# Redesign-8Ch-Mux-Breakout-PMODIA.net
KiCad netlist of a schematic drawn in EAGLE
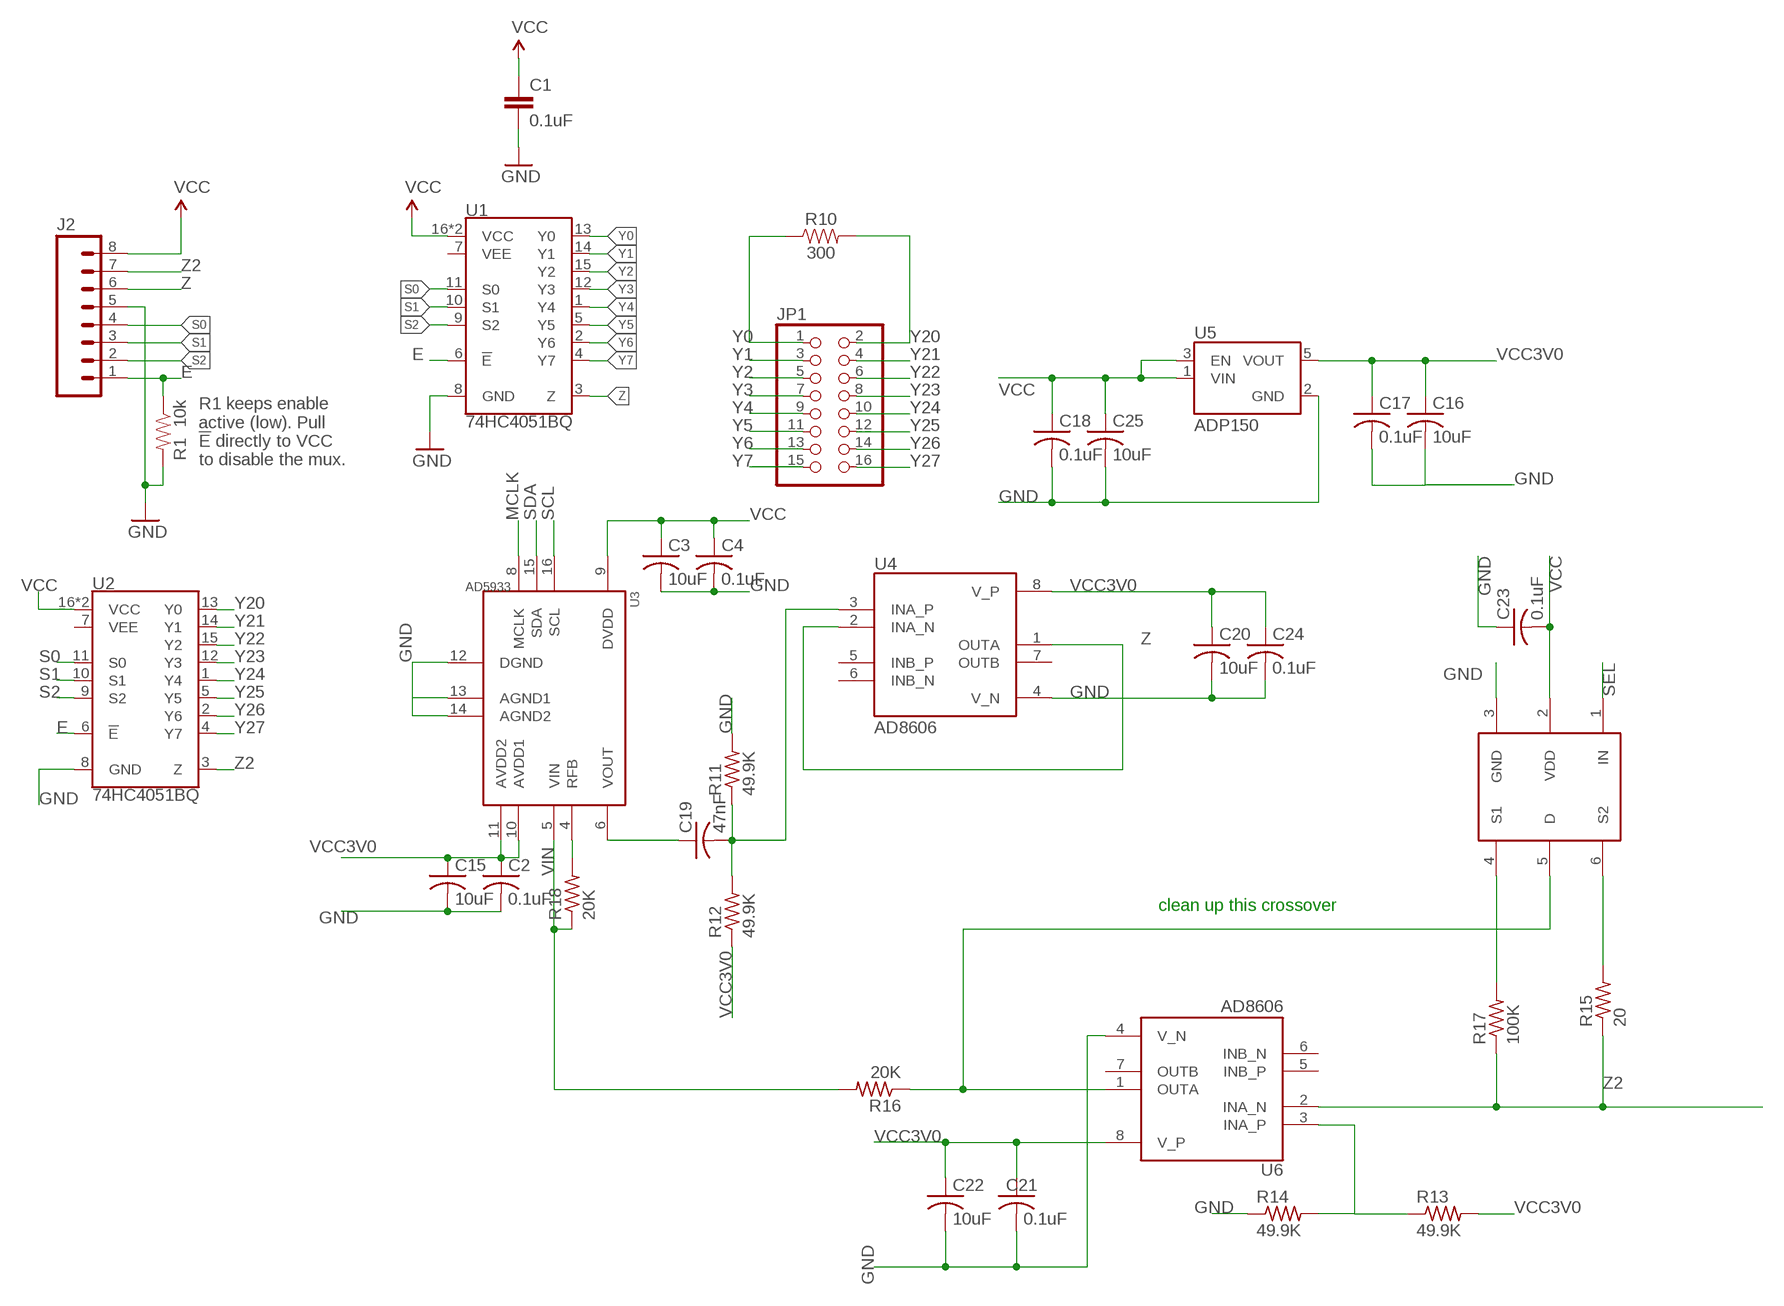
[diagram p0: schematic, sheet 1]

(export (version "E")
  (design (tool "Eeschema 10.0.6"))
  (components
    (comp (ref "C1")
      (value "0.1uF")
      (footprint "eagle-import:0603")
      (libsource (lib "eagle-import") (part "0.1UF-0603-25V-(+80/-20%)"))
    )
    (comp (ref "C2")
      (value "0.1uF")
      (footprint "eagle-import:C0805K")
      (libsource (lib "eagle-import") (part "C-USC0805K"))
    )
    (comp (ref "C3")
      (value "10uF")
      (footprint "eagle-import:C0805K")
      (libsource (lib "eagle-import") (part "C-USC0805K"))
    )
    (comp (ref "C4")
      (value "0.1uF")
      (footprint "eagle-import:C0805K")
      (libsource (lib "eagle-import") (part "C-USC0805K"))
    )
    (comp (ref "C15")
      (value "10uF")
      (footprint "eagle-import:C0805K")
      (libsource (lib "eagle-import") (part "C-USC0805K"))
    )
    (comp (ref "C16")
      (value "10uF")
      (footprint "eagle-import:C0805K")
      (libsource (lib "eagle-import") (part "C-USC0805K"))
    )
    (comp (ref "C17")
      (value "0.1uF")
      (footprint "eagle-import:C0805K")
      (libsource (lib "eagle-import") (part "C-USC0805K"))
    )
    (comp (ref "C18")
      (value "0.1uF")
      (footprint "eagle-import:C0805K")
      (libsource (lib "eagle-import") (part "C-USC0805K"))
    )
    (comp (ref "C19")
      (value "47nF")
      (footprint "eagle-import:C0805K")
      (libsource (lib "eagle-import") (part "C-USC0805K"))
    )
    (comp (ref "C20")
      (value "10uF")
      (footprint "eagle-import:C0805K")
      (libsource (lib "eagle-import") (part "C-USC0805K"))
    )
    (comp (ref "C21")
      (value "0.1uF")
      (footprint "eagle-import:C0805K")
      (libsource (lib "eagle-import") (part "C-USC0805K"))
    )
    (comp (ref "C22")
      (value "10uF")
      (footprint "eagle-import:C0805K")
      (libsource (lib "eagle-import") (part "C-USC0805K"))
    )
    (comp (ref "C23")
      (value "0.1uF")
      (footprint "eagle-import:C0805K")
      (libsource (lib "eagle-import") (part "C-USC0805K"))
    )
    (comp (ref "C24")
      (value "0.1uF")
      (footprint "eagle-import:C0805K")
      (libsource (lib "eagle-import") (part "C-USC0805K"))
    )
    (comp (ref "C25")
      (value "10uF")
      (footprint "eagle-import:C0805K")
      (libsource (lib "eagle-import") (part "C-USC0805K"))
    )
    (comp (ref "J2")
      (value "M08")
      (footprint "eagle-import:1X08_ROUND")
      (libsource (lib "eagle-import") (part "M08"))
    )
    (comp (ref "JP1")
      (value "PINHD-2X8")
      (footprint "eagle-import:2X08")
      (libsource (lib "eagle-import") (part "PINHD-2X8"))
    )
    (comp (ref "R1")
      (value "10k")
      (footprint "eagle-import:0603")
      (libsource (lib "eagle-import") (part "10KOHM-0603-1/10W-1%"))
    )
    (comp (ref "R10")
      (value "300")
      (footprint "eagle-import:0805")
      (libsource (lib "eagle-import") (part "0.3OHM-0805-1/8W-1%"))
    )
    (comp (ref "R11")
      (value "49.9K")
      (footprint "eagle-import:R0603")
      (libsource (lib "eagle-import") (part "R-US_R0603"))
    )
    (comp (ref "R12")
      (value "49.9K")
      (footprint "eagle-import:R0603")
      (libsource (lib "eagle-import") (part "R-US_R0603"))
    )
    (comp (ref "R13")
      (value "49.9K")
      (footprint "eagle-import:R0603")
      (libsource (lib "eagle-import") (part "R-US_R0603"))
    )
    (comp (ref "R14")
      (value "49.9K")
      (footprint "eagle-import:R0603")
      (libsource (lib "eagle-import") (part "R-US_R0603"))
    )
    (comp (ref "R15")
      (value "20")
      (footprint "eagle-import:R0603")
      (libsource (lib "eagle-import") (part "R-US_R0603"))
    )
    (comp (ref "R16")
      (value "20K")
      (footprint "eagle-import:R0603")
      (libsource (lib "eagle-import") (part "R-US_R0603"))
    )
    (comp (ref "R17")
      (value "100K")
      (footprint "eagle-import:R0603")
      (libsource (lib "eagle-import") (part "R-US_R0603"))
    )
    (comp (ref "R18")
      (value "20K")
      (footprint "eagle-import:R0603")
      (libsource (lib "eagle-import") (part "R-US_R0603"))
    )
    (comp (ref "U$1")
      (value "ADG849THROUHG_HOLE")
      (footprint "eagle-import:SOT65P210X110-6N")
      (libsource (lib "eagle-import") (part "ADG849THROUHG_HOLE"))
    )
    (comp (ref "U1")
      (value "74HC4051BQ")
      (footprint "eagle-import:DHVQFN-16-2.5X3.5MM")
      (libsource (lib "eagle-import") (part "74HC4051BQ"))
    )
    (comp (ref "U2")
      (value "74HC4051BQ")
      (footprint "eagle-import:DHVQFN-16-2.5X3.5MM")
      (libsource (lib "eagle-import") (part "74HC4051BQ"))
    )
    (comp (ref "U3")
      (value "AD5933")
      (footprint "eagle-import:SSOP16")
      (libsource (lib "eagle-import") (part "AD5933"))
    )
    (comp (ref "U4")
      (value "AD8606")
      (footprint "eagle-import:SOIC-8")
      (fields (field (name "MF") "Analog Devices") (field (name "MP") "AD8606ARZ"))
      (libsource (lib "eagle-import") (part "Updated PMODIA_AD8606"))
    )
    (comp (ref "U5")
      (value "ADP150")
      (footprint "eagle-import:SOT95P280X100-5N")
      (fields (field (name "MF") "Analog Devices") (field (name "MP") "ADP150AUJZ-2.0-R7"))
      (libsource (lib "eagle-import") (part "ADP150"))
    )
    (comp (ref "U6")
      (value "AD8606")
      (footprint "eagle-import:SOIC-8")
      (fields (field (name "MF") "Analog Devices") (field (name "MP") "AD8606ARZ"))
      (libsource (lib "eagle-import") (part "Updated PMODIA_AD8606"))
    )
  )
  (nets
    (net (code "1") (name "/E") (class "Default")
      (node (ref "J2") (pin "1") (pinfunction "1_1") (pintype "passive"))
      (node (ref "R1") (pin "1") (pinfunction "1_1") (pintype "passive"))
      (node (ref "U1") (pin "6") (pinfunction "~{E}_6") (pintype "bidirectional"))
      (node (ref "U2") (pin "6") (pinfunction "~{E}_6") (pintype "bidirectional"))
    )
    (net (code "2") (name "/MCLK") (class "Default")
      (node (ref "U3") (pin "8") (pinfunction "MCLK_8") (pintype "bidirectional"))
    )
    (net (code "3") (name "/SCL") (class "Default")
      (node (ref "U3") (pin "16") (pinfunction "SCL_16") (pintype "bidirectional"))
    )
    (net (code "4") (name "/SDA") (class "Default")
      (node (ref "U3") (pin "15") (pinfunction "SDA_15") (pintype "bidirectional"))
    )
    (net (code "5") (name "/SEL") (class "Default")
      (node (ref "U$1") (pin "1") (pinfunction "IN_1") (pintype "bidirectional"))
    )
    (net (code "6") (name "/VCC3V0") (class "Default")
      (node (ref "C15") (pin "1") (pinfunction "1_1") (pintype "passive"))
      (node (ref "C16") (pin "1") (pinfunction "1_1") (pintype "passive"))
      (node (ref "C17") (pin "1") (pinfunction "1_1") (pintype "passive"))
      (node (ref "C2") (pin "1") (pinfunction "1_1") (pintype "passive"))
      (node (ref "C20") (pin "1") (pinfunction "1_1") (pintype "passive"))
      (node (ref "C21") (pin "1") (pinfunction "1_1") (pintype "passive"))
      (node (ref "C22") (pin "1") (pinfunction "1_1") (pintype "passive"))
      (node (ref "C24") (pin "1") (pinfunction "1_1") (pintype "passive"))
      (node (ref "R12") (pin "1") (pinfunction "1_1") (pintype "passive"))
      (node (ref "R13") (pin "2") (pinfunction "2_2") (pintype "passive"))
      (node (ref "U3") (pin "10") (pinfunction "AVDD1_10") (pintype "bidirectional"))
      (node (ref "U3") (pin "11") (pinfunction "AVDD2_11") (pintype "bidirectional"))
      (node (ref "U4") (pin "8") (pinfunction "V_P_8") (pintype "power_in"))
      (node (ref "U5") (pin "5") (pinfunction "VOUT_5") (pintype "output"))
      (node (ref "U6") (pin "8") (pinfunction "V_P_8") (pintype "power_in"))
    )
    (net (code "7") (name "/VIN") (class "Default")
      (node (ref "R16") (pin "2") (pinfunction "2_2") (pintype "passive"))
      (node (ref "R18") (pin "1") (pinfunction "1_1") (pintype "passive"))
      (node (ref "U3") (pin "5") (pinfunction "VIN_5") (pintype "bidirectional"))
    )
    (net (code "8") (name "/Y20") (class "Default")
      (node (ref "JP1") (pin "2") (pinfunction "2_2") (pintype "passive"))
      (node (ref "R10") (pin "2") (pinfunction "2_2") (pintype "passive"))
      (node (ref "U2") (pin "13") (pinfunction "Y0_13") (pintype "bidirectional"))
    )
    (net (code "9") (name "/Y21") (class "Default")
      (node (ref "JP1") (pin "4") (pinfunction "4_4") (pintype "passive"))
      (node (ref "U2") (pin "14") (pinfunction "Y1_14") (pintype "bidirectional"))
    )
    (net (code "10") (name "/Y22") (class "Default")
      (node (ref "JP1") (pin "6") (pinfunction "6_6") (pintype "passive"))
      (node (ref "U2") (pin "15") (pinfunction "Y2_15") (pintype "bidirectional"))
    )
    (net (code "11") (name "/Y23") (class "Default")
      (node (ref "JP1") (pin "8") (pinfunction "8_8") (pintype "passive"))
      (node (ref "U2") (pin "12") (pinfunction "Y3_12") (pintype "bidirectional"))
    )
    (net (code "12") (name "/Y24") (class "Default")
      (node (ref "JP1") (pin "10") (pinfunction "10_10") (pintype "passive"))
      (node (ref "U2") (pin "1") (pinfunction "Y4_1") (pintype "bidirectional"))
    )
    (net (code "13") (name "/Y25") (class "Default")
      (node (ref "JP1") (pin "12") (pinfunction "12_12") (pintype "passive"))
      (node (ref "U2") (pin "5") (pinfunction "Y5_5") (pintype "bidirectional"))
    )
    (net (code "14") (name "/Y26") (class "Default")
      (node (ref "JP1") (pin "14") (pinfunction "14_14") (pintype "passive"))
      (node (ref "U2") (pin "2") (pinfunction "Y6_2") (pintype "bidirectional"))
    )
    (net (code "15") (name "/Y27") (class "Default")
      (node (ref "JP1") (pin "16") (pinfunction "16_16") (pintype "passive"))
      (node (ref "U2") (pin "4") (pinfunction "Y7_4") (pintype "bidirectional"))
    )
    (net (code "16") (name "/Z2") (class "Default")
      (node (ref "J2") (pin "7") (pinfunction "7_7") (pintype "passive"))
      (node (ref "R15") (pin "1") (pinfunction "1_1") (pintype "passive"))
      (node (ref "R17") (pin "1") (pinfunction "1_1") (pintype "passive"))
      (node (ref "U2") (pin "3") (pinfunction "Z_3") (pintype "bidirectional"))
      (node (ref "U6") (pin "2") (pinfunction "INA_N_2") (pintype "input"))
    )
    (net (code "17") (name "GND") (class "Default")
      (node (ref "C1") (pin "2") (pinfunction "2_2") (pintype "passive"))
      (node (ref "C15") (pin "2") (pinfunction "2_2") (pintype "passive"))
      (node (ref "C16") (pin "2") (pinfunction "2_2") (pintype "passive"))
      (node (ref "C17") (pin "2") (pinfunction "2_2") (pintype "passive"))
      (node (ref "C18") (pin "2") (pinfunction "2_2") (pintype "passive"))
      (node (ref "C2") (pin "2") (pinfunction "2_2") (pintype "passive"))
      (node (ref "C20") (pin "2") (pinfunction "2_2") (pintype "passive"))
      (node (ref "C21") (pin "2") (pinfunction "2_2") (pintype "passive"))
      (node (ref "C22") (pin "2") (pinfunction "2_2") (pintype "passive"))
      (node (ref "C23") (pin "1") (pinfunction "1_1") (pintype "passive"))
      (node (ref "C24") (pin "2") (pinfunction "2_2") (pintype "passive"))
      (node (ref "C25") (pin "2") (pinfunction "2_2") (pintype "passive"))
      (node (ref "C3") (pin "2") (pinfunction "2_2") (pintype "passive"))
      (node (ref "C4") (pin "2") (pinfunction "2_2") (pintype "passive"))
      (node (ref "J2") (pin "5") (pinfunction "5_5") (pintype "passive"))
      (node (ref "R1") (pin "2") (pinfunction "2_2") (pintype "passive"))
      (node (ref "R11") (pin "2") (pinfunction "2_2") (pintype "passive"))
      (node (ref "R14") (pin "1") (pinfunction "1_1") (pintype "passive"))
      (node (ref "U$1") (pin "3") (pinfunction "GND_3") (pintype "bidirectional"))
      (node (ref "U1") (pin "8") (pinfunction "GND_8") (pintype "bidirectional"))
      (node (ref "U2") (pin "8") (pinfunction "GND_8") (pintype "bidirectional"))
      (node (ref "U3") (pin "12") (pinfunction "DGND_12") (pintype "bidirectional"))
      (node (ref "U3") (pin "14") (pinfunction "AGND2_14") (pintype "bidirectional"))
      (node (ref "U4") (pin "4") (pinfunction "V_N_4") (pintype "power_in"))
      (node (ref "U5") (pin "2") (pinfunction "GND_2") (pintype "power_in"))
      (node (ref "U6") (pin "4") (pinfunction "V_N_4") (pintype "power_in"))
    )
    (net (code "18") (name "Net-(U$1-D)") (class "Default")
      (node (ref "R16") (pin "1") (pinfunction "1_1") (pintype "passive"))
      (node (ref "U$1") (pin "5") (pinfunction "D_5") (pintype "bidirectional"))
      (node (ref "U6") (pin "1") (pinfunction "OUTA_1") (pintype "input"))
    )
    (net (code "19") (name "Net-(U$1-S1)") (class "Default")
      (node (ref "R17") (pin "2") (pinfunction "2_2") (pintype "passive"))
      (node (ref "U$1") (pin "4") (pinfunction "S1_4") (pintype "bidirectional"))
    )
    (net (code "20") (name "Net-(U$1-S2)") (class "Default")
      (node (ref "R15") (pin "2") (pinfunction "2_2") (pintype "passive"))
      (node (ref "U$1") (pin "6") (pinfunction "S2_6") (pintype "bidirectional"))
    )
    (net (code "21") (name "Net-(U3-RFB)") (class "Default")
      (node (ref "R18") (pin "2") (pinfunction "2_2") (pintype "passive"))
      (node (ref "U3") (pin "4") (pinfunction "RFB_4") (pintype "bidirectional"))
    )
    (net (code "22") (name "Net-(U3-VOUT)") (class "Default")
      (node (ref "C19") (pin "1") (pinfunction "1_1") (pintype "passive"))
      (node (ref "U3") (pin "6") (pinfunction "VOUT_6") (pintype "bidirectional"))
    )
    (net (code "23") (name "Net-(U4-INA_P)") (class "Default")
      (node (ref "C19") (pin "2") (pinfunction "2_2") (pintype "passive"))
      (node (ref "R11") (pin "1") (pinfunction "1_1") (pintype "passive"))
      (node (ref "R12") (pin "2") (pinfunction "2_2") (pintype "passive"))
      (node (ref "U4") (pin "3") (pinfunction "INA_P_3") (pintype "input"))
    )
    (net (code "24") (name "Net-(U6-INA_P)") (class "Default")
      (node (ref "R13") (pin "1") (pinfunction "1_1") (pintype "passive"))
      (node (ref "R14") (pin "2") (pinfunction "2_2") (pintype "passive"))
      (node (ref "U6") (pin "3") (pinfunction "INA_P_3") (pintype "input"))
    )
    (net (code "25") (name "S0") (class "Default")
      (node (ref "J2") (pin "4") (pinfunction "4_4") (pintype "passive"))
      (node (ref "U1") (pin "11") (pinfunction "S0_11") (pintype "bidirectional"))
      (node (ref "U2") (pin "11") (pinfunction "S0_11") (pintype "bidirectional"))
    )
    (net (code "26") (name "S1") (class "Default")
      (node (ref "J2") (pin "3") (pinfunction "3_3") (pintype "passive"))
      (node (ref "U1") (pin "10") (pinfunction "S1_10") (pintype "bidirectional"))
      (node (ref "U2") (pin "10") (pinfunction "S1_10") (pintype "bidirectional"))
    )
    (net (code "27") (name "S2") (class "Default")
      (node (ref "J2") (pin "2") (pinfunction "2_2") (pintype "passive"))
      (node (ref "U1") (pin "9") (pinfunction "S2_9") (pintype "bidirectional"))
      (node (ref "U2") (pin "9") (pinfunction "S2_9") (pintype "bidirectional"))
    )
    (net (code "28") (name "VCC") (class "Default")
      (node (ref "C1") (pin "1") (pinfunction "1_1") (pintype "passive"))
      (node (ref "C18") (pin "1") (pinfunction "1_1") (pintype "passive"))
      (node (ref "C23") (pin "2") (pinfunction "2_2") (pintype "passive"))
      (node (ref "C25") (pin "1") (pinfunction "1_1") (pintype "passive"))
      (node (ref "C3") (pin "1") (pinfunction "1_1") (pintype "passive"))
      (node (ref "C4") (pin "1") (pinfunction "1_1") (pintype "passive"))
      (node (ref "J2") (pin "8") (pinfunction "8_8") (pintype "passive"))
      (node (ref "U$1") (pin "2") (pinfunction "VDD_2") (pintype "bidirectional"))
      (node (ref "U1") (pin "16") (pinfunction "VCC_16") (pintype "bidirectional"))
      (node (ref "U1") (pin "EP") (pinfunction "VCC_EP") (pintype "bidirectional"))
      (node (ref "U2") (pin "16") (pinfunction "VCC_16") (pintype "bidirectional"))
      (node (ref "U2") (pin "EP") (pinfunction "VCC_EP") (pintype "bidirectional"))
      (node (ref "U3") (pin "9") (pinfunction "DVDD_9") (pintype "bidirectional"))
      (node (ref "U5") (pin "1") (pinfunction "VIN_1") (pintype "input"))
      (node (ref "U5") (pin "3") (pinfunction "EN_3") (pintype "input"))
    )
    (net (code "29") (name "Y0") (class "Default")
      (node (ref "JP1") (pin "1") (pinfunction "1_1") (pintype "passive"))
      (node (ref "R10") (pin "1") (pinfunction "1_1") (pintype "passive"))
      (node (ref "U1") (pin "13") (pinfunction "Y0_13") (pintype "bidirectional"))
    )
    (net (code "30") (name "Y1") (class "Default")
      (node (ref "JP1") (pin "3") (pinfunction "3_3") (pintype "passive"))
      (node (ref "U1") (pin "14") (pinfunction "Y1_14") (pintype "bidirectional"))
    )
    (net (code "31") (name "Y2") (class "Default")
      (node (ref "JP1") (pin "5") (pinfunction "5_5") (pintype "passive"))
      (node (ref "U1") (pin "15") (pinfunction "Y2_15") (pintype "bidirectional"))
    )
    (net (code "32") (name "Y3") (class "Default")
      (node (ref "JP1") (pin "7") (pinfunction "7_7") (pintype "passive"))
      (node (ref "U1") (pin "12") (pinfunction "Y3_12") (pintype "bidirectional"))
    )
    (net (code "33") (name "Y4") (class "Default")
      (node (ref "JP1") (pin "9") (pinfunction "9_9") (pintype "passive"))
      (node (ref "U1") (pin "1") (pinfunction "Y4_1") (pintype "bidirectional"))
    )
    (net (code "34") (name "Y5") (class "Default")
      (node (ref "JP1") (pin "11") (pinfunction "11_11") (pintype "passive"))
      (node (ref "U1") (pin "5") (pinfunction "Y5_5") (pintype "bidirectional"))
    )
    (net (code "35") (name "Y6") (class "Default")
      (node (ref "JP1") (pin "13") (pinfunction "13_13") (pintype "passive"))
      (node (ref "U1") (pin "2") (pinfunction "Y6_2") (pintype "bidirectional"))
    )
    (net (code "36") (name "Y7") (class "Default")
      (node (ref "JP1") (pin "15") (pinfunction "15_15") (pintype "passive"))
      (node (ref "U1") (pin "4") (pinfunction "Y7_4") (pintype "bidirectional"))
    )
    (net (code "37") (name "Z") (class "Default")
      (node (ref "J2") (pin "6") (pinfunction "6_6") (pintype "passive"))
      (node (ref "U1") (pin "3") (pinfunction "Z_3") (pintype "bidirectional"))
      (node (ref "U4") (pin "1") (pinfunction "OUTA_1") (pintype "input"))
      (node (ref "U4") (pin "2") (pinfunction "INA_N_2") (pintype "input"))
    )
    (net (code "38") (name "unconnected-(U1-VEE-Pad7)") (class "Default")
      (node (ref "U1") (pin "7") (pinfunction "VEE_7") (pintype "bidirectional"))
    )
    (net (code "39") (name "unconnected-(U2-VEE-Pad7)") (class "Default")
      (node (ref "U2") (pin "7") (pinfunction "VEE_7") (pintype "bidirectional"))
    )
    (net (code "40") (name "unconnected-(U3-AGND1-Pad13)") (class "Default")
      (node (ref "U3") (pin "13") (pinfunction "AGND1_13") (pintype "bidirectional"))
    )
    (net (code "41") (name "unconnected-(U4-INB_N-Pad6)") (class "Default")
      (node (ref "U4") (pin "6") (pinfunction "INB_N_6") (pintype "input"))
    )
    (net (code "42") (name "unconnected-(U4-INB_P-Pad5)") (class "Default")
      (node (ref "U4") (pin "5") (pinfunction "INB_P_5") (pintype "input"))
    )
    (net (code "43") (name "unconnected-(U4-OUTB-Pad7)") (class "Default")
      (node (ref "U4") (pin "7") (pinfunction "OUTB_7") (pintype "input"))
    )
    (net (code "44") (name "unconnected-(U6-INB_N-Pad6)") (class "Default")
      (node (ref "U6") (pin "6") (pinfunction "INB_N_6") (pintype "input"))
    )
    (net (code "45") (name "unconnected-(U6-INB_P-Pad5)") (class "Default")
      (node (ref "U6") (pin "5") (pinfunction "INB_P_5") (pintype "input"))
    )
    (net (code "46") (name "unconnected-(U6-OUTB-Pad7)") (class "Default")
      (node (ref "U6") (pin "7") (pinfunction "OUTB_7") (pintype "input"))
    )
  )
)
